# EtchaSketch.net
KiCad netlist of a schematic drawn in EAGLE
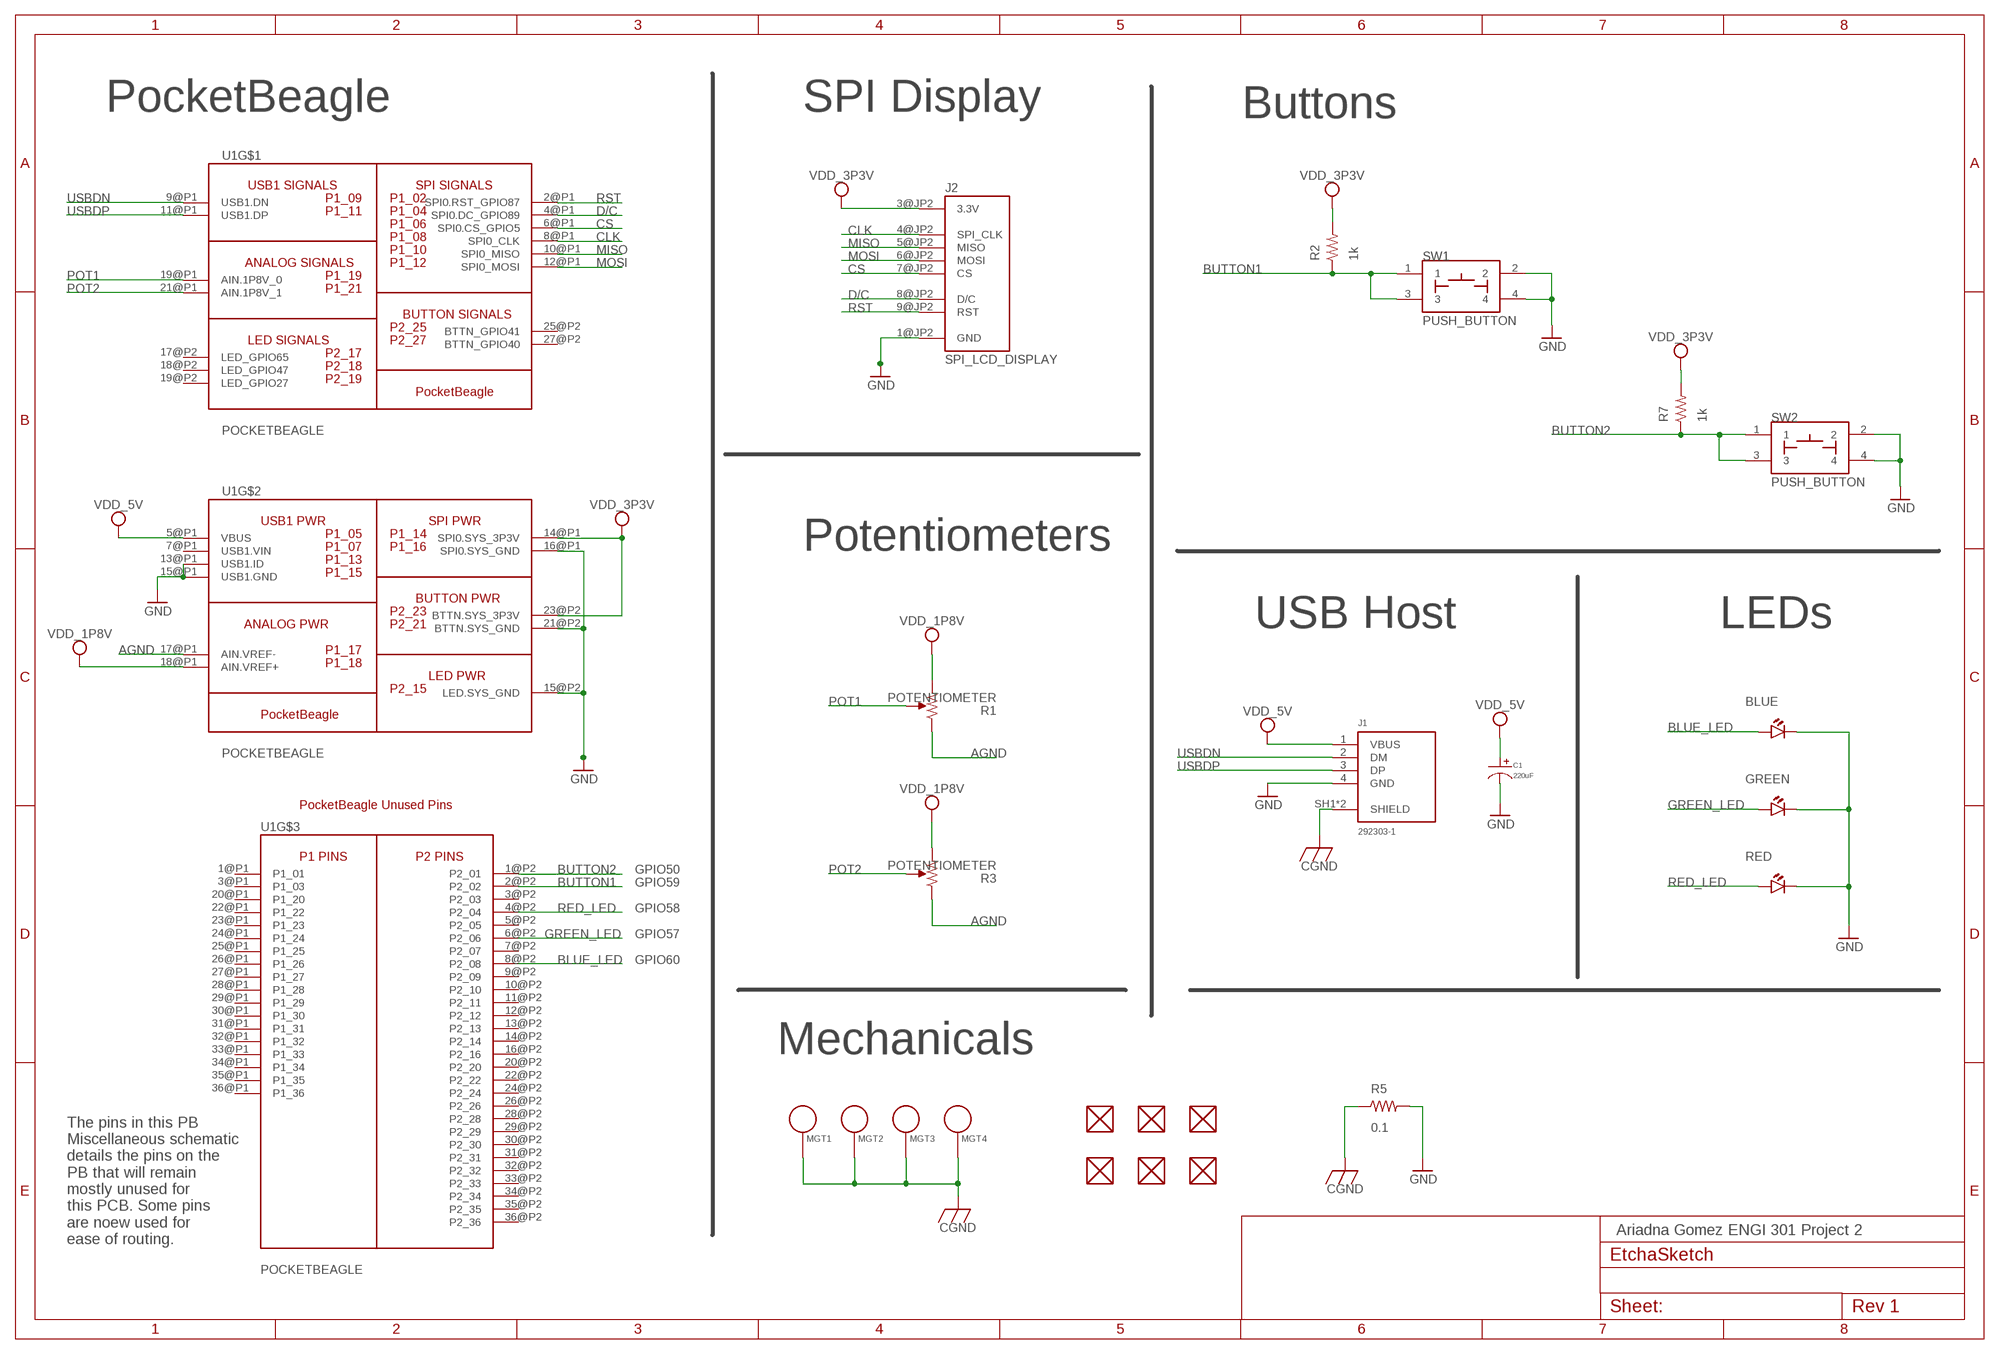
[diagram p0: schematic, sheet 1]

(export (version "E")
  (design (tool "Eeschema 10.0.6"))
  (components
    (comp (ref "BLUE")
      (value "LED")
      (footprint "eagle-import:EIA-STD")
      (libsource (lib "eagle-import") (part "LED"))
    )
    (comp (ref "C1")
      (value "220uF")
      (footprint "eagle-import:CP10MM")
      (libsource (lib "eagle-import") (part "CAPACITOR_P_10MM"))
    )
    (comp (ref "FUD1")
      (value "FIDUCIAL")
      (footprint "eagle-import:FIDUCIAL_40MIL")
      (libsource (lib "eagle-import") (part "FIDUCIAL"))
    )
    (comp (ref "FUD2")
      (value "FIDUCIAL")
      (footprint "eagle-import:FIDUCIAL_40MIL")
      (libsource (lib "eagle-import") (part "FIDUCIAL"))
    )
    (comp (ref "FUD3")
      (value "FIDUCIAL")
      (footprint "eagle-import:FIDUCIAL_40MIL")
      (libsource (lib "eagle-import") (part "FIDUCIAL"))
    )
    (comp (ref "FUD4")
      (value "FIDUCIAL")
      (footprint "eagle-import:FIDUCIAL_40MIL")
      (libsource (lib "eagle-import") (part "FIDUCIAL"))
    )
    (comp (ref "FUD5")
      (value "FIDUCIAL")
      (footprint "eagle-import:FIDUCIAL_40MIL")
      (libsource (lib "eagle-import") (part "FIDUCIAL"))
    )
    (comp (ref "FUD6")
      (value "FIDUCIAL")
      (footprint "eagle-import:FIDUCIAL_40MIL")
      (libsource (lib "eagle-import") (part "FIDUCIAL"))
    )
    (comp (ref "GREEN")
      (value "LED")
      (footprint "eagle-import:EIA-STD")
      (libsource (lib "eagle-import") (part "LED"))
    )
    (comp (ref "J1")
      (value "292303-1")
      (footprint "eagle-import:TE_292303-1")
      (fields (field (name "MF") "TE Connectivity"))
      (libsource (lib "eagle-import") (part "292303-1"))
    )
    (comp (ref "J2")
      (value "SPI_LCD_DISPLAY")
      (footprint "eagle-import:SPI_LCD_DISPLAY")
      (libsource (lib "eagle-import") (part "SPI_LCD_DISPLAY"))
    )
    (comp (ref "MGT1")
      (value "MOUNTING_HOLE")
      (footprint "eagle-import:MOUNTING_HOLE")
      (libsource (lib "eagle-import") (part "MOUNTING_HOLE"))
    )
    (comp (ref "MGT2")
      (value "MOUNTING_HOLE")
      (footprint "eagle-import:MOUNTING_HOLE")
      (libsource (lib "eagle-import") (part "MOUNTING_HOLE"))
    )
    (comp (ref "MGT3")
      (value "MOUNTING_HOLE")
      (footprint "eagle-import:MOUNTING_HOLE")
      (libsource (lib "eagle-import") (part "MOUNTING_HOLE"))
    )
    (comp (ref "MGT4")
      (value "MOUNTING_HOLE")
      (footprint "eagle-import:MOUNTING_HOLE")
      (libsource (lib "eagle-import") (part "MOUNTING_HOLE"))
    )
    (comp (ref "R1")
      (value "POTENTIOMETER")
      (footprint "eagle-import:POT-PO90S")
      (libsource (lib "eagle-import") (part "POTENTIOMETER"))
    )
    (comp (ref "R2")
      (value "1k")
      (footprint "eagle-import:R0603")
      (libsource (lib "eagle-import") (part "R_R0603"))
    )
    (comp (ref "R3")
      (value "POTENTIOMETER")
      (footprint "eagle-import:POT-PO90S")
      (libsource (lib "eagle-import") (part "POTENTIOMETER"))
    )
    (comp (ref "R5")
      (value "0.1")
      (footprint "eagle-import:R0805")
      (libsource (lib "eagle-import") (part "combo_lock_R_R0805"))
    )
    (comp (ref "R7")
      (value "1k")
      (footprint "eagle-import:R0603")
      (libsource (lib "eagle-import") (part "R_R0603"))
    )
    (comp (ref "RED")
      (value "LED")
      (footprint "eagle-import:EIA-STD")
      (libsource (lib "eagle-import") (part "LED"))
    )
    (comp (ref "SW1")
      (value "PUSH_BUTTON")
      (footprint "eagle-import:BUTTON_12.5MM")
      (libsource (lib "eagle-import") (part "PUSH_BUTTON"))
    )
    (comp (ref "SW2")
      (value "PUSH_BUTTON")
      (footprint "eagle-import:BUTTON_12.5MM")
      (libsource (lib "eagle-import") (part "PUSH_BUTTON"))
    )
    (comp (ref "U1")
      (value "POCKETBEAGLE")
      (footprint "eagle-import:POCKETBEAGLE")
      (libsource (lib "eagle-import") (part "POCKETBEAGLE"))
    )
  )
  (nets
    (net (code "1") (name "/AGND") (class "Default")
      (node (ref "R1") (pin "CCW") (pinfunction "CCW_CCW") (pintype "passive"))
      (node (ref "R3") (pin "CCW") (pinfunction "CCW_CCW") (pintype "passive"))
      (node (ref "U1") (pin "17@P1") (pinfunction "AIN.VREF-_17@P1") (pintype "bidirectional"))
    )
    (net (code "2") (name "/BLUE_LED") (class "Default")
      (node (ref "BLUE") (pin "ANODE") (pinfunction "ANODE_ANODE") (pintype "bidirectional"))
      (node (ref "U1") (pin "8@P2") (pinfunction "P2_08_8@P2") (pintype "bidirectional"))
    )
    (net (code "3") (name "/BUTTON1") (class "Default")
      (node (ref "R2") (pin "1") (pinfunction "1_1") (pintype "passive"))
      (node (ref "SW1") (pin "1") (pinfunction "1_1") (pintype "bidirectional"))
      (node (ref "SW1") (pin "3") (pinfunction "3_3") (pintype "bidirectional"))
      (node (ref "U1") (pin "2@P2") (pinfunction "P2_02_2@P2") (pintype "bidirectional"))
    )
    (net (code "4") (name "/BUTTON2") (class "Default")
      (node (ref "R7") (pin "1") (pinfunction "1_1") (pintype "passive"))
      (node (ref "SW2") (pin "1") (pinfunction "1_1") (pintype "bidirectional"))
      (node (ref "SW2") (pin "3") (pinfunction "3_3") (pintype "bidirectional"))
      (node (ref "U1") (pin "1@P2") (pinfunction "P2_01_1@P2") (pintype "bidirectional"))
    )
    (net (code "5") (name "/CLK") (class "Default")
      (node (ref "J2") (pin "4@JP2") (pinfunction "SPI_CLK_4@JP2") (pintype "bidirectional"))
      (node (ref "U1") (pin "8@P1") (pinfunction "SPI0_CLK_8@P1") (pintype "bidirectional"))
    )
    (net (code "6") (name "/CS") (class "Default")
      (node (ref "J2") (pin "7@JP2") (pinfunction "CS_7@JP2") (pintype "bidirectional"))
      (node (ref "U1") (pin "6@P1") (pinfunction "SPI0.CS_GPIO5_6@P1") (pintype "bidirectional"))
    )
    (net (code "7") (name "/D{slash}C") (class "Default")
      (node (ref "J2") (pin "8@JP2") (pinfunction "D/C_8@JP2") (pintype "bidirectional"))
      (node (ref "U1") (pin "4@P1") (pinfunction "SPI0.DC_GPIO89_4@P1") (pintype "bidirectional"))
    )
    (net (code "8") (name "/GREEN_LED") (class "Default")
      (node (ref "GREEN") (pin "ANODE") (pinfunction "ANODE_ANODE") (pintype "bidirectional"))
      (node (ref "U1") (pin "6@P2") (pinfunction "P2_06_6@P2") (pintype "bidirectional"))
    )
    (net (code "9") (name "/MISO") (class "Default")
      (node (ref "J2") (pin "5@JP2") (pinfunction "MISO_5@JP2") (pintype "bidirectional"))
      (node (ref "U1") (pin "10@P1") (pinfunction "SPI0_MISO_10@P1") (pintype "bidirectional"))
    )
    (net (code "10") (name "/MOSI") (class "Default")
      (node (ref "J2") (pin "6@JP2") (pinfunction "MOSI_6@JP2") (pintype "bidirectional"))
      (node (ref "U1") (pin "12@P1") (pinfunction "SPI0_MOSI_12@P1") (pintype "bidirectional"))
    )
    (net (code "11") (name "/POT1") (class "Default")
      (node (ref "R1") (pin "S") (pinfunction "S_S") (pintype "bidirectional"))
      (node (ref "U1") (pin "19@P1") (pinfunction "AIN.1P8V_0_19@P1") (pintype "bidirectional"))
    )
    (net (code "12") (name "/POT2") (class "Default")
      (node (ref "R3") (pin "S") (pinfunction "S_S") (pintype "bidirectional"))
      (node (ref "U1") (pin "21@P1") (pinfunction "AIN.1P8V_1_21@P1") (pintype "bidirectional"))
    )
    (net (code "13") (name "/RED_LED") (class "Default")
      (node (ref "RED") (pin "ANODE") (pinfunction "ANODE_ANODE") (pintype "bidirectional"))
      (node (ref "U1") (pin "4@P2") (pinfunction "P2_04_4@P2") (pintype "bidirectional"))
    )
    (net (code "14") (name "/RST") (class "Default")
      (node (ref "J2") (pin "9@JP2") (pinfunction "RST_9@JP2") (pintype "bidirectional"))
      (node (ref "U1") (pin "2@P1") (pinfunction "SPI0.RST_GPIO87_2@P1") (pintype "bidirectional"))
    )
    (net (code "15") (name "/USBDN") (class "Default")
      (node (ref "J1") (pin "2") (pinfunction "DM_2") (pintype "passive"))
      (node (ref "U1") (pin "9@P1") (pinfunction "USB1.DN_9@P1") (pintype "bidirectional"))
    )
    (net (code "16") (name "/USBDP") (class "Default")
      (node (ref "J1") (pin "3") (pinfunction "DP_3") (pintype "passive"))
      (node (ref "U1") (pin "11@P1") (pinfunction "USB1.DP_11@P1") (pintype "bidirectional"))
    )
    (net (code "17") (name "CGND") (class "Default")
      (node (ref "J1") (pin "SH1") (pinfunction "SHIELD_SH1") (pintype "passive"))
      (node (ref "J1") (pin "SH2") (pinfunction "SHIELD_SH2") (pintype "passive"))
      (node (ref "MGT1") (pin "P$1") (pinfunction "P$1_P$1") (pintype "bidirectional"))
      (node (ref "MGT2") (pin "P$1") (pinfunction "P$1_P$1") (pintype "bidirectional"))
      (node (ref "MGT3") (pin "P$1") (pinfunction "P$1_P$1") (pintype "bidirectional"))
      (node (ref "MGT4") (pin "P$1") (pinfunction "P$1_P$1") (pintype "bidirectional"))
      (node (ref "R5") (pin "1") (pinfunction "1_1") (pintype "passive"))
    )
    (net (code "18") (name "GND") (class "Default")
      (node (ref "BLUE") (pin "CATHODE") (pinfunction "CATHODE_CATHODE") (pintype "bidirectional"))
      (node (ref "C1") (pin "P$2") (pinfunction "P$2_P$2") (pintype "passive"))
      (node (ref "GREEN") (pin "CATHODE") (pinfunction "CATHODE_CATHODE") (pintype "bidirectional"))
      (node (ref "J1") (pin "4") (pinfunction "GND_4") (pintype "passive"))
      (node (ref "J2") (pin "1@JP2") (pinfunction "GND_1@JP2") (pintype "bidirectional"))
      (node (ref "R5") (pin "2") (pinfunction "2_2") (pintype "passive"))
      (node (ref "RED") (pin "CATHODE") (pinfunction "CATHODE_CATHODE") (pintype "bidirectional"))
      (node (ref "SW1") (pin "2") (pinfunction "2_2") (pintype "bidirectional"))
      (node (ref "SW1") (pin "4") (pinfunction "4_4") (pintype "bidirectional"))
      (node (ref "SW2") (pin "2") (pinfunction "2_2") (pintype "bidirectional"))
      (node (ref "SW2") (pin "4") (pinfunction "4_4") (pintype "bidirectional"))
      (node (ref "U1") (pin "13@P1") (pinfunction "USB1.ID_13@P1") (pintype "bidirectional"))
      (node (ref "U1") (pin "15@P1") (pinfunction "USB1.GND_15@P1") (pintype "bidirectional"))
      (node (ref "U1") (pin "15@P2") (pinfunction "LED.SYS_GND_15@P2") (pintype "bidirectional"))
      (node (ref "U1") (pin "16@P1") (pinfunction "SPI0.SYS_GND_16@P1") (pintype "bidirectional"))
      (node (ref "U1") (pin "21@P2") (pinfunction "BTTN.SYS_GND_21@P2") (pintype "bidirectional"))
    )
    (net (code "19") (name "VDD_1P8V") (class "Default")
      (node (ref "R1") (pin "CW") (pinfunction "CW_CW") (pintype "passive"))
      (node (ref "R3") (pin "CW") (pinfunction "CW_CW") (pintype "passive"))
      (node (ref "U1") (pin "18@P1") (pinfunction "AIN.VREF+_18@P1") (pintype "power_in"))
    )
    (net (code "20") (name "VDD_3P3V") (class "Default")
      (node (ref "J2") (pin "3@JP2") (pinfunction "3.3V_3@JP2") (pintype "bidirectional"))
      (node (ref "R2") (pin "2") (pinfunction "2_2") (pintype "passive"))
      (node (ref "R7") (pin "2") (pinfunction "2_2") (pintype "passive"))
      (node (ref "U1") (pin "14@P1") (pinfunction "SPI0.SYS_3P3V_14@P1") (pintype "power_in"))
      (node (ref "U1") (pin "23@P2") (pinfunction "BTTN.SYS_3P3V_23@P2") (pintype "power_in"))
    )
    (net (code "21") (name "VDD_5V") (class "Default")
      (node (ref "C1") (pin "P$1") (pinfunction "P$1_P$1") (pintype "passive"))
      (node (ref "J1") (pin "1") (pinfunction "VBUS_1") (pintype "passive"))
      (node (ref "U1") (pin "5@P1") (pinfunction "VBUS_5@P1") (pintype "power_in"))
    )
    (net (code "22") (name "unconnected-(FUD1-PadP$1)") (class "Default")
      (node (ref "FUD1") (pin "P$1") (pinfunction "P$1_P$1") (pintype "no_connect"))
    )
    (net (code "23") (name "unconnected-(FUD2-PadP$1)") (class "Default")
      (node (ref "FUD2") (pin "P$1") (pinfunction "P$1_P$1") (pintype "no_connect"))
    )
    (net (code "24") (name "unconnected-(FUD3-PadP$1)") (class "Default")
      (node (ref "FUD3") (pin "P$1") (pinfunction "P$1_P$1") (pintype "no_connect"))
    )
    (net (code "25") (name "unconnected-(FUD4-PadP$1)") (class "Default")
      (node (ref "FUD4") (pin "P$1") (pinfunction "P$1_P$1") (pintype "no_connect"))
    )
    (net (code "26") (name "unconnected-(FUD5-PadP$1)") (class "Default")
      (node (ref "FUD5") (pin "P$1") (pinfunction "P$1_P$1") (pintype "no_connect"))
    )
    (net (code "27") (name "unconnected-(FUD6-PadP$1)") (class "Default")
      (node (ref "FUD6") (pin "P$1") (pinfunction "P$1_P$1") (pintype "no_connect"))
    )
    (net (code "28") (name "unconnected-(U1A-BTTN_GPIO40-Pad27@P2)") (class "Default")
      (node (ref "U1") (pin "27@P2") (pinfunction "BTTN_GPIO40_27@P2") (pintype "bidirectional"))
    )
    (net (code "29") (name "unconnected-(U1A-BTTN_GPIO41-Pad25@P2)") (class "Default")
      (node (ref "U1") (pin "25@P2") (pinfunction "BTTN_GPIO41_25@P2") (pintype "bidirectional"))
    )
    (net (code "30") (name "unconnected-(U1A-LED_GPIO27-Pad19@P2)") (class "Default")
      (node (ref "U1") (pin "19@P2") (pinfunction "LED_GPIO27_19@P2") (pintype "bidirectional"))
    )
    (net (code "31") (name "unconnected-(U1A-LED_GPIO47-Pad18@P2)") (class "Default")
      (node (ref "U1") (pin "18@P2") (pinfunction "LED_GPIO47_18@P2") (pintype "bidirectional"))
    )
    (net (code "32") (name "unconnected-(U1A-LED_GPIO65-Pad17@P2)") (class "Default")
      (node (ref "U1") (pin "17@P2") (pinfunction "LED_GPIO65_17@P2") (pintype "bidirectional"))
    )
    (net (code "33") (name "unconnected-(U1B-USB1.VIN-Pad7@P1)") (class "Default")
      (node (ref "U1") (pin "7@P1") (pinfunction "USB1.VIN_7@P1") (pintype "bidirectional"))
    )
    (net (code "34") (name "unconnected-(U1C-P1_01-Pad1@P1)") (class "Default")
      (node (ref "U1") (pin "1@P1") (pinfunction "P1_01_1@P1") (pintype "bidirectional"))
    )
    (net (code "35") (name "unconnected-(U1C-P1_03-Pad3@P1)") (class "Default")
      (node (ref "U1") (pin "3@P1") (pinfunction "P1_03_3@P1") (pintype "bidirectional"))
    )
    (net (code "36") (name "unconnected-(U1C-P1_20-Pad20@P1)") (class "Default")
      (node (ref "U1") (pin "20@P1") (pinfunction "P1_20_20@P1") (pintype "bidirectional"))
    )
    (net (code "37") (name "unconnected-(U1C-P1_22-Pad22@P1)") (class "Default")
      (node (ref "U1") (pin "22@P1") (pinfunction "P1_22_22@P1") (pintype "bidirectional"))
    )
    (net (code "38") (name "unconnected-(U1C-P1_23-Pad23@P1)") (class "Default")
      (node (ref "U1") (pin "23@P1") (pinfunction "P1_23_23@P1") (pintype "bidirectional"))
    )
    (net (code "39") (name "unconnected-(U1C-P1_24-Pad24@P1)") (class "Default")
      (node (ref "U1") (pin "24@P1") (pinfunction "P1_24_24@P1") (pintype "bidirectional"))
    )
    (net (code "40") (name "unconnected-(U1C-P1_25-Pad25@P1)") (class "Default")
      (node (ref "U1") (pin "25@P1") (pinfunction "P1_25_25@P1") (pintype "bidirectional"))
    )
    (net (code "41") (name "unconnected-(U1C-P1_26-Pad26@P1)") (class "Default")
      (node (ref "U1") (pin "26@P1") (pinfunction "P1_26_26@P1") (pintype "bidirectional"))
    )
    (net (code "42") (name "unconnected-(U1C-P1_27-Pad27@P1)") (class "Default")
      (node (ref "U1") (pin "27@P1") (pinfunction "P1_27_27@P1") (pintype "bidirectional"))
    )
    (net (code "43") (name "unconnected-(U1C-P1_28-Pad28@P1)") (class "Default")
      (node (ref "U1") (pin "28@P1") (pinfunction "P1_28_28@P1") (pintype "bidirectional"))
    )
    (net (code "44") (name "unconnected-(U1C-P1_29-Pad29@P1)") (class "Default")
      (node (ref "U1") (pin "29@P1") (pinfunction "P1_29_29@P1") (pintype "bidirectional"))
    )
    (net (code "45") (name "unconnected-(U1C-P1_30-Pad30@P1)") (class "Default")
      (node (ref "U1") (pin "30@P1") (pinfunction "P1_30_30@P1") (pintype "bidirectional"))
    )
    (net (code "46") (name "unconnected-(U1C-P1_31-Pad31@P1)") (class "Default")
      (node (ref "U1") (pin "31@P1") (pinfunction "P1_31_31@P1") (pintype "bidirectional"))
    )
    (net (code "47") (name "unconnected-(U1C-P1_32-Pad32@P1)") (class "Default")
      (node (ref "U1") (pin "32@P1") (pinfunction "P1_32_32@P1") (pintype "bidirectional"))
    )
    (net (code "48") (name "unconnected-(U1C-P1_33-Pad33@P1)") (class "Default")
      (node (ref "U1") (pin "33@P1") (pinfunction "P1_33_33@P1") (pintype "bidirectional"))
    )
    (net (code "49") (name "unconnected-(U1C-P1_34-Pad34@P1)") (class "Default")
      (node (ref "U1") (pin "34@P1") (pinfunction "P1_34_34@P1") (pintype "bidirectional"))
    )
    (net (code "50") (name "unconnected-(U1C-P1_35-Pad35@P1)") (class "Default")
      (node (ref "U1") (pin "35@P1") (pinfunction "P1_35_35@P1") (pintype "bidirectional"))
    )
    (net (code "51") (name "unconnected-(U1C-P1_36-Pad36@P1)") (class "Default")
      (node (ref "U1") (pin "36@P1") (pinfunction "P1_36_36@P1") (pintype "bidirectional"))
    )
    (net (code "52") (name "unconnected-(U1C-P2_03-Pad3@P2)") (class "Default")
      (node (ref "U1") (pin "3@P2") (pinfunction "P2_03_3@P2") (pintype "bidirectional"))
    )
    (net (code "53") (name "unconnected-(U1C-P2_05-Pad5@P2)") (class "Default")
      (node (ref "U1") (pin "5@P2") (pinfunction "P2_05_5@P2") (pintype "bidirectional"))
    )
    (net (code "54") (name "unconnected-(U1C-P2_07-Pad7@P2)") (class "Default")
      (node (ref "U1") (pin "7@P2") (pinfunction "P2_07_7@P2") (pintype "bidirectional"))
    )
    (net (code "55") (name "unconnected-(U1C-P2_09-Pad9@P2)") (class "Default")
      (node (ref "U1") (pin "9@P2") (pinfunction "P2_09_9@P2") (pintype "bidirectional"))
    )
    (net (code "56") (name "unconnected-(U1C-P2_10-Pad10@P2)") (class "Default")
      (node (ref "U1") (pin "10@P2") (pinfunction "P2_10_10@P2") (pintype "bidirectional"))
    )
    (net (code "57") (name "unconnected-(U1C-P2_11-Pad11@P2)") (class "Default")
      (node (ref "U1") (pin "11@P2") (pinfunction "P2_11_11@P2") (pintype "bidirectional"))
    )
    (net (code "58") (name "unconnected-(U1C-P2_12-Pad12@P2)") (class "Default")
      (node (ref "U1") (pin "12@P2") (pinfunction "P2_12_12@P2") (pintype "bidirectional"))
    )
    (net (code "59") (name "unconnected-(U1C-P2_13-Pad13@P2)") (class "Default")
      (node (ref "U1") (pin "13@P2") (pinfunction "P2_13_13@P2") (pintype "bidirectional"))
    )
    (net (code "60") (name "unconnected-(U1C-P2_14-Pad14@P2)") (class "Default")
      (node (ref "U1") (pin "14@P2") (pinfunction "P2_14_14@P2") (pintype "bidirectional"))
    )
    (net (code "61") (name "unconnected-(U1C-P2_16-Pad16@P2)") (class "Default")
      (node (ref "U1") (pin "16@P2") (pinfunction "P2_16_16@P2") (pintype "bidirectional"))
    )
    (net (code "62") (name "unconnected-(U1C-P2_20-Pad20@P2)") (class "Default")
      (node (ref "U1") (pin "20@P2") (pinfunction "P2_20_20@P2") (pintype "bidirectional"))
    )
    (net (code "63") (name "unconnected-(U1C-P2_22-Pad22@P2)") (class "Default")
      (node (ref "U1") (pin "22@P2") (pinfunction "P2_22_22@P2") (pintype "bidirectional"))
    )
    (net (code "64") (name "unconnected-(U1C-P2_24-Pad24@P2)") (class "Default")
      (node (ref "U1") (pin "24@P2") (pinfunction "P2_24_24@P2") (pintype "bidirectional"))
    )
    (net (code "65") (name "unconnected-(U1C-P2_26-Pad26@P2)") (class "Default")
      (node (ref "U1") (pin "26@P2") (pinfunction "P2_26_26@P2") (pintype "bidirectional"))
    )
    (net (code "66") (name "unconnected-(U1C-P2_28-Pad28@P2)") (class "Default")
      (node (ref "U1") (pin "28@P2") (pinfunction "P2_28_28@P2") (pintype "bidirectional"))
    )
    (net (code "67") (name "unconnected-(U1C-P2_29-Pad29@P2)") (class "Default")
      (node (ref "U1") (pin "29@P2") (pinfunction "P2_29_29@P2") (pintype "bidirectional"))
    )
    (net (code "68") (name "unconnected-(U1C-P2_30-Pad30@P2)") (class "Default")
      (node (ref "U1") (pin "30@P2") (pinfunction "P2_30_30@P2") (pintype "bidirectional"))
    )
    (net (code "69") (name "unconnected-(U1C-P2_31-Pad31@P2)") (class "Default")
      (node (ref "U1") (pin "31@P2") (pinfunction "P2_31_31@P2") (pintype "bidirectional"))
    )
    (net (code "70") (name "unconnected-(U1C-P2_32-Pad32@P2)") (class "Default")
      (node (ref "U1") (pin "32@P2") (pinfunction "P2_32_32@P2") (pintype "bidirectional"))
    )
    (net (code "71") (name "unconnected-(U1C-P2_33-Pad33@P2)") (class "Default")
      (node (ref "U1") (pin "33@P2") (pinfunction "P2_33_33@P2") (pintype "bidirectional"))
    )
    (net (code "72") (name "unconnected-(U1C-P2_34-Pad34@P2)") (class "Default")
      (node (ref "U1") (pin "34@P2") (pinfunction "P2_34_34@P2") (pintype "bidirectional"))
    )
    (net (code "73") (name "unconnected-(U1C-P2_35-Pad35@P2)") (class "Default")
      (node (ref "U1") (pin "35@P2") (pinfunction "P2_35_35@P2") (pintype "bidirectional"))
    )
    (net (code "74") (name "unconnected-(U1C-P2_36-Pad36@P2)") (class "Default")
      (node (ref "U1") (pin "36@P2") (pinfunction "P2_36_36@P2") (pintype "bidirectional"))
    )
  )
)
